# Relays.net
KiCad netlist of a schematic drawn in Altium Designer
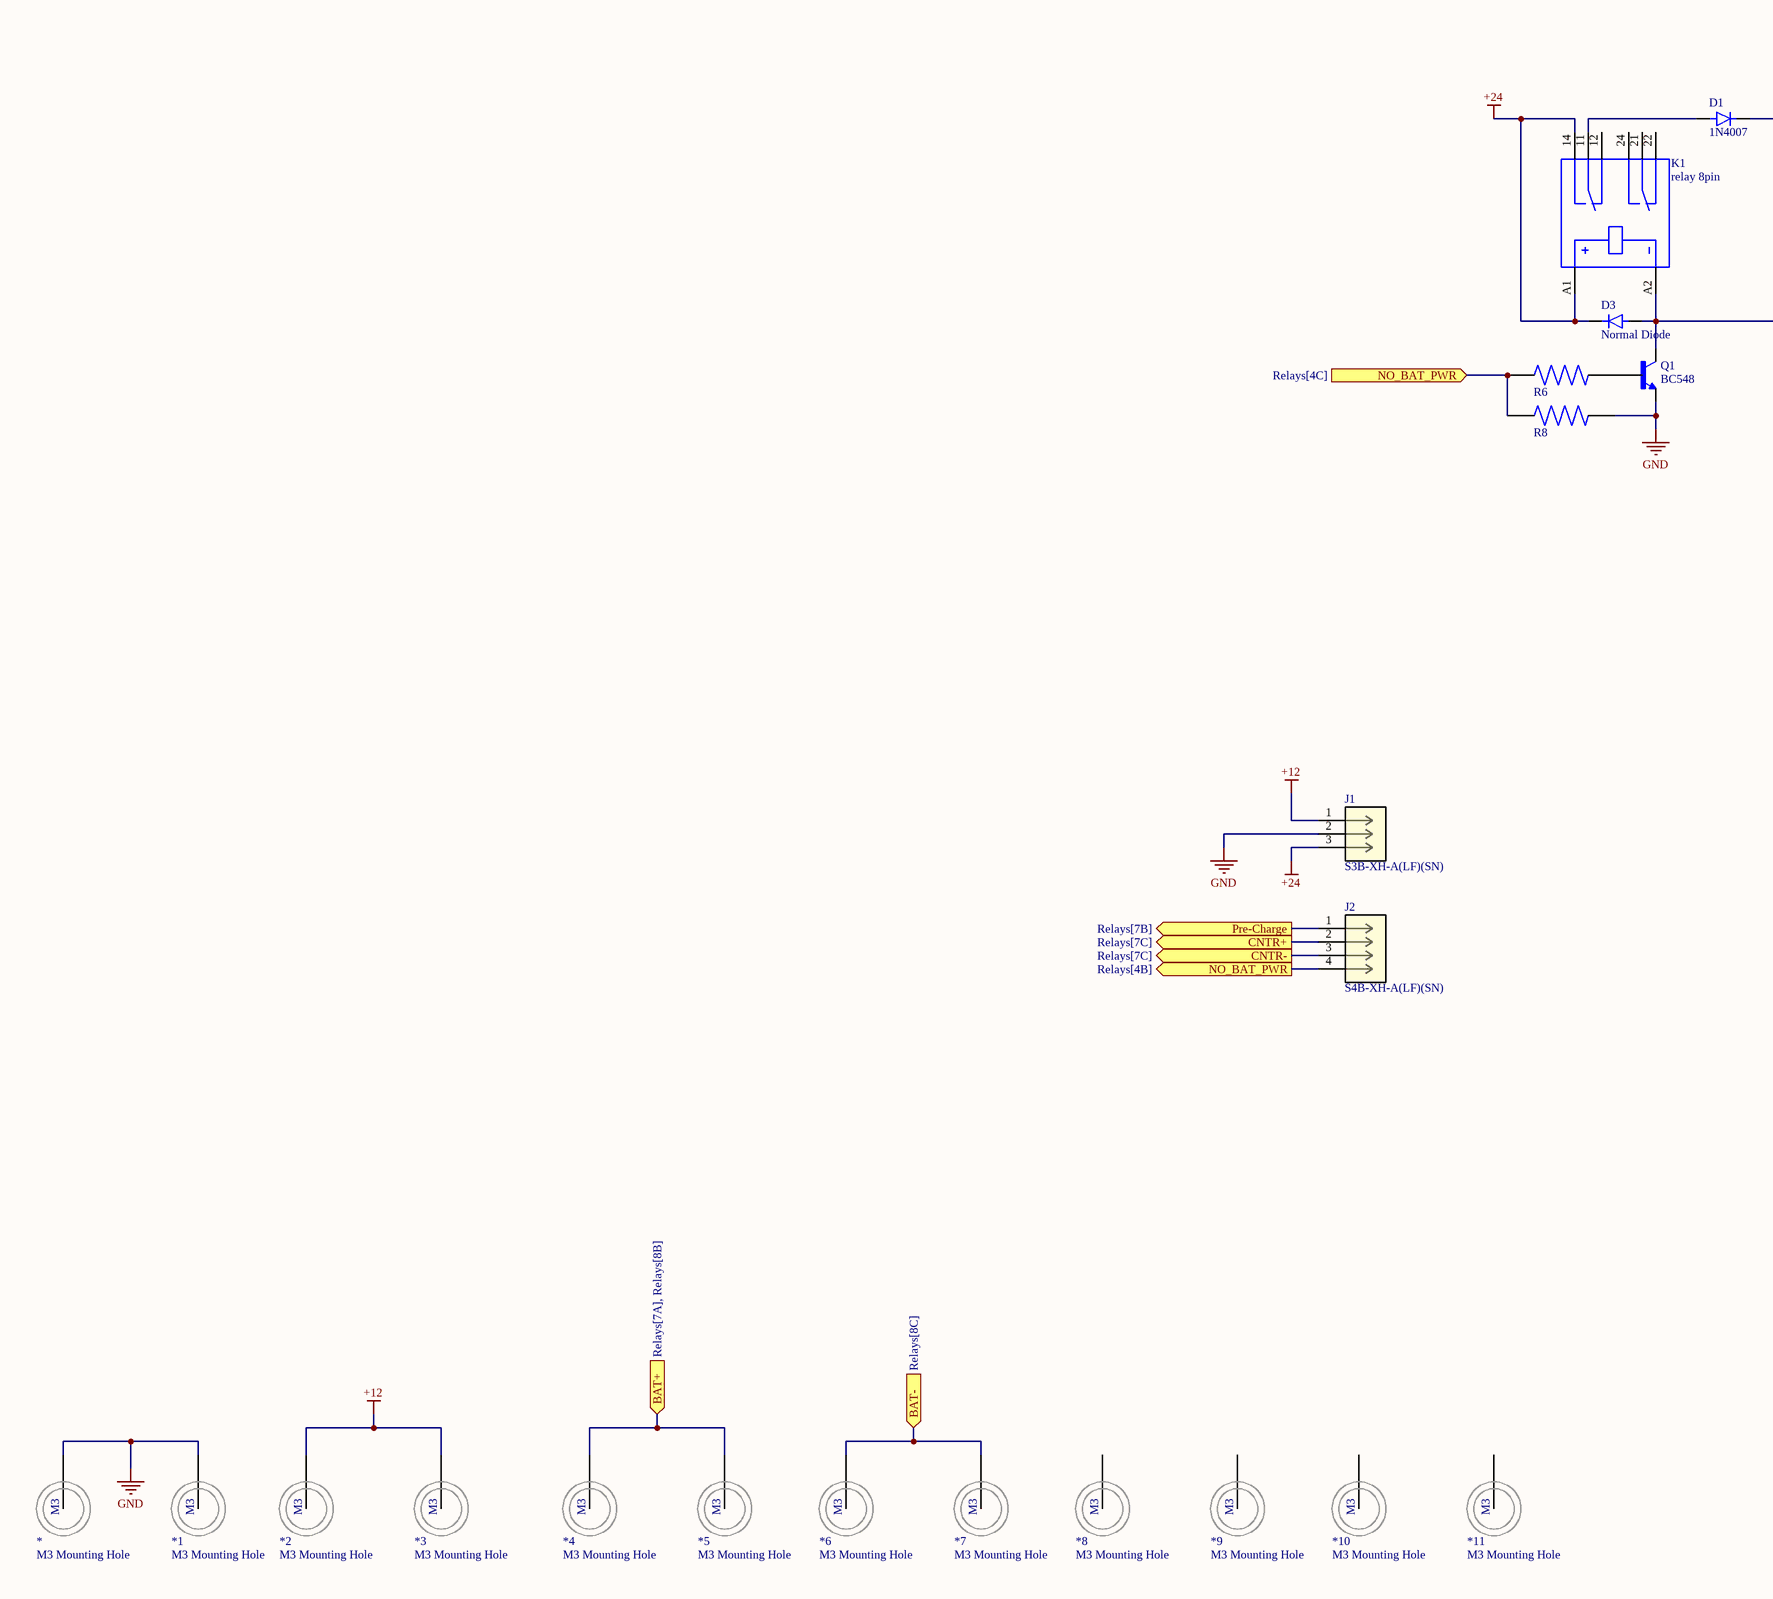
[diagram p0: Relays.SchDoc, left]
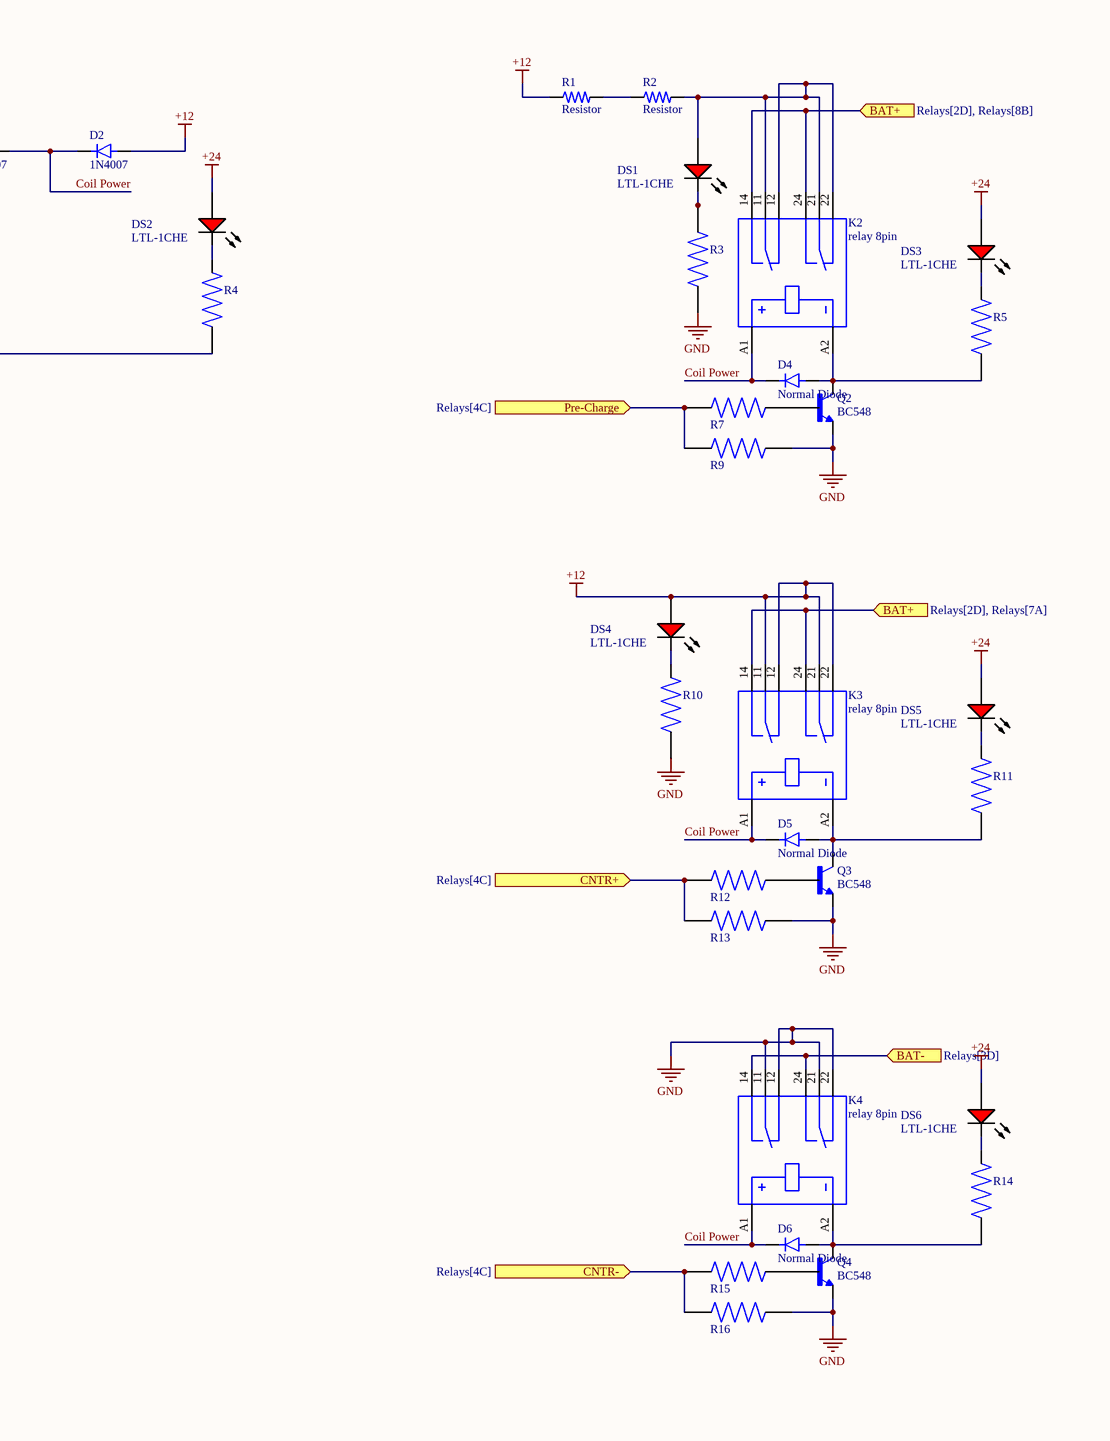
[diagram p1: Relays.SchDoc, right]

(export (version "E")
  (design (tool "Eeschema 10.0.6"))
  (components
    (comp (ref "*")
      (value "M3 Mounting Hole")
      (footprint "M3 - Mounting Hole")
      (libsource (lib "Connectors Through Hole") (part "M3 Mounting Hole"))
    )
    (comp (ref "*1")
      (value "M3 Mounting Hole")
      (footprint "M3 - Mounting Hole")
      (libsource (lib "Connectors Through Hole") (part "M3 Mounting Hole"))
    )
    (comp (ref "*2")
      (value "M3 Mounting Hole")
      (footprint "M3 - Mounting Hole")
      (libsource (lib "Connectors Through Hole") (part "M3 Mounting Hole"))
    )
    (comp (ref "*3")
      (value "M3 Mounting Hole")
      (footprint "M3 - Mounting Hole")
      (libsource (lib "Connectors Through Hole") (part "M3 Mounting Hole"))
    )
    (comp (ref "*4")
      (value "M3 Mounting Hole")
      (footprint "M3 - Mounting Hole")
      (libsource (lib "Connectors Through Hole") (part "M3 Mounting Hole"))
    )
    (comp (ref "*5")
      (value "M3 Mounting Hole")
      (footprint "M3 - Mounting Hole")
      (libsource (lib "Connectors Through Hole") (part "M3 Mounting Hole"))
    )
    (comp (ref "*6")
      (value "M3 Mounting Hole")
      (footprint "M3 - Mounting Hole")
      (libsource (lib "Connectors Through Hole") (part "M3 Mounting Hole"))
    )
    (comp (ref "*7")
      (value "M3 Mounting Hole")
      (footprint "M3 - Mounting Hole")
      (libsource (lib "Connectors Through Hole") (part "M3 Mounting Hole"))
    )
    (comp (ref "*8")
      (value "M3 Mounting Hole")
      (footprint "M3 - Mounting Hole")
      (libsource (lib "Connectors Through Hole") (part "M3 Mounting Hole"))
    )
    (comp (ref "*9")
      (value "M3 Mounting Hole")
      (footprint "M3 - Mounting Hole")
      (libsource (lib "Connectors Through Hole") (part "M3 Mounting Hole"))
    )
    (comp (ref "*10")
      (value "M3 Mounting Hole")
      (footprint "M3 - Mounting Hole")
      (libsource (lib "Connectors Through Hole") (part "M3 Mounting Hole"))
    )
    (comp (ref "*11")
      (value "M3 Mounting Hole")
      (footprint "M3 - Mounting Hole")
      (libsource (lib "Connectors Through Hole") (part "M3 Mounting Hole"))
    )
    (comp (ref "D1")
      (value "1N4007")
      (footprint "Common Trhough Hole")
      (fields (field (name "MF") "NTE Electronics, Inc."))
      (libsource (lib "Diodes Through Hole") (part "Normal Diode"))
    )
    (comp (ref "D2")
      (value "1N4007")
      (footprint "Common Trhough Hole")
      (fields (field (name "MF") "NTE Electronics, Inc."))
      (libsource (lib "Diodes Through Hole") (part "Normal Diode"))
    )
    (comp (ref "D3")
      (value "Normal Diode")
      (footprint "Common Trhough Hole")
      (fields (field (name "MF") "NTE Electronics, Inc.") (field (name "MP") "1N4007"))
      (libsource (lib "Diodes Through Hole") (part "Normal Diode"))
    )
    (comp (ref "D4")
      (value "Normal Diode")
      (footprint "Common Trhough Hole")
      (fields (field (name "MF") "NTE Electronics, Inc.") (field (name "MP") "1N4007"))
      (libsource (lib "Diodes Through Hole") (part "Normal Diode"))
    )
    (comp (ref "D5")
      (value "Normal Diode")
      (footprint "Common Trhough Hole")
      (fields (field (name "MF") "NTE Electronics, Inc.") (field (name "MP") "1N4007"))
      (libsource (lib "Diodes Through Hole") (part "Normal Diode"))
    )
    (comp (ref "D6")
      (value "Normal Diode")
      (footprint "Common Trhough Hole")
      (fields (field (name "MF") "NTE Electronics, Inc.") (field (name "MP") "1N4007"))
      (libsource (lib "Diodes Through Hole") (part "Normal Diode"))
    )
    (comp (ref "DS1")
      (value "LTL-1CHE")
      (footprint "LED_3mm")
      (description "Radial LED, 12.6 mcd, 20 mA, 2 V, -55 to 100 degC, 2-Pin THD, RoHS, Bulk")
      (fields (field (name "TOLERANCE") "20%"))
      (libsource (lib "MySCH_Library") (part "RED_LED 3mm"))
    )
    (comp (ref "DS2")
      (value "LTL-1CHE")
      (footprint "LED_3mm")
      (description "Radial LED, 12.6 mcd, 20 mA, 2 V, -55 to 100 degC, 2-Pin THD, RoHS, Bulk")
      (fields (field (name "TOLERANCE") "20%"))
      (libsource (lib "MySCH_Library") (part "RED_LED 3mm"))
    )
    (comp (ref "DS3")
      (value "LTL-1CHE")
      (footprint "LED_3mm")
      (description "Radial LED, 12.6 mcd, 20 mA, 2 V, -55 to 100 degC, 2-Pin THD, RoHS, Bulk")
      (fields (field (name "TOLERANCE") "20%"))
      (libsource (lib "MySCH_Library") (part "RED_LED 3mm"))
    )
    (comp (ref "DS4")
      (value "LTL-1CHE")
      (footprint "LED_3mm")
      (description "Radial LED, 12.6 mcd, 20 mA, 2 V, -55 to 100 degC, 2-Pin THD, RoHS, Bulk")
      (fields (field (name "TOLERANCE") "20%"))
      (libsource (lib "MySCH_Library") (part "RED_LED 3mm"))
    )
    (comp (ref "DS5")
      (value "LTL-1CHE")
      (footprint "LED_3mm")
      (description "Radial LED, 12.6 mcd, 20 mA, 2 V, -55 to 100 degC, 2-Pin THD, RoHS, Bulk")
      (fields (field (name "TOLERANCE") "20%"))
      (libsource (lib "MySCH_Library") (part "RED_LED 3mm"))
    )
    (comp (ref "DS6")
      (value "LTL-1CHE")
      (footprint "LED_3mm")
      (description "Radial LED, 12.6 mcd, 20 mA, 2 V, -55 to 100 degC, 2-Pin THD, RoHS, Bulk")
      (fields (field (name "TOLERANCE") "20%"))
      (libsource (lib "MySCH_Library") (part "RED_LED 3mm"))
    )
    (comp (ref "J1")
      (value "S3B-XH-A(LF)(SN)")
      (footprint "3P JST XH2.54mm 90º")
      (description "No Description Available")
      (fields (field (name "COPYRIGHT") "Copyright (C) 2024 Ultra Librarian. All rights reserved."))
      (libsource (lib "Connectors Through Hole") (part "3P JST XH2.54mm 90º"))
    )
    (comp (ref "J2")
      (value "S4B-XH-A(LF)(SN)")
      (footprint "4P JST XH2.54mm 90º")
      (description "No Description Available")
      (fields (field (name "COPYRIGHT") "Copyright (C) 2024 Ultra Librarian. All rights reserved."))
      (libsource (lib "Connectors Through Hole") (part "4P JST XH2.54mm 90º"))
    )
    (comp (ref "K1")
      (value "relay 8pin")
      (footprint "Relay socket 8pin")
      (description "General Purpose Relay DPDT _2 Form C_ 24VDC Coil Through Hole")
      (fields (field (name "MF") "TE Connectivity") (field (name "MP") "1-1393243-0"))
      (libsource (lib "MySCH_Library") (part "relay 8pin"))
    )
    (comp (ref "K2")
      (value "relay 8pin")
      (footprint "Relay socket 8pin")
      (description "General Purpose Relay DPDT _2 Form C_ 24VDC Coil Through Hole")
      (fields (field (name "MF") "TE Connectivity") (field (name "MP") "1-1393243-0"))
      (libsource (lib "MySCH_Library") (part "relay 8pin"))
    )
    (comp (ref "K3")
      (value "relay 8pin")
      (footprint "Relay socket 8pin")
      (description "General Purpose Relay DPDT _2 Form C_ 24VDC Coil Through Hole")
      (fields (field (name "MF") "TE Connectivity") (field (name "MP") "1-1393243-0"))
      (libsource (lib "MySCH_Library") (part "relay 8pin"))
    )
    (comp (ref "K4")
      (value "relay 8pin")
      (footprint "Relay socket 8pin")
      (description "General Purpose Relay DPDT _2 Form C_ 24VDC Coil Through Hole")
      (fields (field (name "MF") "TE Connectivity") (field (name "MP") "1-1393243-0"))
      (libsource (lib "MySCH_Library") (part "relay 8pin"))
    )
    (comp (ref "Q1")
      (value "BC548")
      (footprint "bc548")
      (description "Bipolar (BJT) Transistor NPN 30V 100mA 300MHz 500mW Through Hole TO-92-3")
      (fields (field (name "MF") "ON Semiconductor"))
      (libsource (lib "MySCH_Library") (part "BC548"))
    )
    (comp (ref "Q2")
      (value "BC548")
      (footprint "bc548")
      (description "Bipolar (BJT) Transistor NPN 30V 100mA 300MHz 500mW Through Hole TO-92-3")
      (fields (field (name "MF") "ON Semiconductor"))
      (libsource (lib "MySCH_Library") (part "BC548"))
    )
    (comp (ref "Q3")
      (value "BC548")
      (footprint "bc548")
      (description "Bipolar (BJT) Transistor NPN 30V 100mA 300MHz 500mW Through Hole TO-92-3")
      (fields (field (name "MF") "ON Semiconductor"))
      (libsource (lib "MySCH_Library") (part "BC548"))
    )
    (comp (ref "Q4")
      (value "BC548")
      (footprint "bc548")
      (description "Bipolar (BJT) Transistor NPN 30V 100mA 300MHz 500mW Through Hole TO-92-3")
      (fields (field (name "MF") "ON Semiconductor"))
      (libsource (lib "MySCH_Library") (part "BC548"))
    )
    (comp (ref "R1")
      (value "Resistor")
      (footprint "Resistor_Through Hole")
      (fields
        (field (name "MP") "2-2176053-0")
        (field (name "TOLERANCE") "1%")
        (field (name "MF") "TE Connectivity")
      )
      (libsource (lib "Resistors Through Hole") (part "Resistor"))
    )
    (comp (ref "R2")
      (value "Resistor")
      (footprint "Resistor_Through Hole")
      (fields
        (field (name "MP") "2-2176053-0")
        (field (name "TOLERANCE") "1%")
        (field (name "MF") "TE Connectivity")
      )
      (libsource (lib "Resistors Through Hole") (part "Resistor"))
    )
    (comp (ref "R3")
      (value "Resistor_Through Hole")
      (footprint "Resistor_Through Hole")
      (description "1.02 Ohms Â±1% 0.25W, 1/4W Through Hole Resistor Axial Metal Film")
      (fields (field (name "MP") "MFR-25FTE52-1R") (field (name "MF") "Yageo"))
      (libsource (lib "MySCH_Library") (part "Resistor_Through Hole"))
    )
    (comp (ref "R4")
      (value "Resistor_Through Hole")
      (footprint "Resistor_Through Hole")
      (description "1.02 Ohms Â±1% 0.25W, 1/4W Through Hole Resistor Axial Metal Film")
      (fields (field (name "MP") "MFR-25FTE52-1R") (field (name "MF") "Yageo"))
      (libsource (lib "MySCH_Library") (part "Resistor_Through Hole"))
    )
    (comp (ref "R5")
      (value "Resistor_Through Hole")
      (footprint "Resistor_Through Hole")
      (description "1.02 Ohms Â±1% 0.25W, 1/4W Through Hole Resistor Axial Metal Film")
      (fields (field (name "MP") "MFR-25FTE52-1R") (field (name "MF") "Yageo"))
      (libsource (lib "MySCH_Library") (part "Resistor_Through Hole"))
    )
    (comp (ref "R6")
      (value "Resistor_Through Hole")
      (footprint "Resistor_Through Hole")
      (description "1.02 Ohms Â±1% 0.25W, 1/4W Through Hole Resistor Axial Metal Film")
      (fields (field (name "MP") "MFR-25FTE52-1R") (field (name "MF") "Yageo"))
      (libsource (lib "MySCH_Library") (part "Resistor_Through Hole"))
    )
    (comp (ref "R7")
      (value "Resistor_Through Hole")
      (footprint "Resistor_Through Hole")
      (description "1.02 Ohms Â±1% 0.25W, 1/4W Through Hole Resistor Axial Metal Film")
      (fields (field (name "MP") "MFR-25FTE52-1R") (field (name "MF") "Yageo"))
      (libsource (lib "MySCH_Library") (part "Resistor_Through Hole"))
    )
    (comp (ref "R8")
      (value "Resistor_Through Hole")
      (footprint "Resistor_Through Hole")
      (description "1.02 Ohms Â±1% 0.25W, 1/4W Through Hole Resistor Axial Metal Film")
      (fields (field (name "MP") "MFR-25FTE52-1R") (field (name "MF") "Yageo"))
      (libsource (lib "MySCH_Library") (part "Resistor_Through Hole"))
    )
    (comp (ref "R9")
      (value "Resistor_Through Hole")
      (footprint "Resistor_Through Hole")
      (description "1.02 Ohms Â±1% 0.25W, 1/4W Through Hole Resistor Axial Metal Film")
      (fields (field (name "MP") "MFR-25FTE52-1R") (field (name "MF") "Yageo"))
      (libsource (lib "MySCH_Library") (part "Resistor_Through Hole"))
    )
    (comp (ref "R10")
      (value "Resistor_Through Hole")
      (footprint "Resistor_Through Hole")
      (description "1.02 Ohms Â±1% 0.25W, 1/4W Through Hole Resistor Axial Metal Film")
      (fields (field (name "MP") "MFR-25FTE52-1R") (field (name "MF") "Yageo"))
      (libsource (lib "MySCH_Library") (part "Resistor_Through Hole"))
    )
    (comp (ref "R11")
      (value "Resistor_Through Hole")
      (footprint "Resistor_Through Hole")
      (description "1.02 Ohms Â±1% 0.25W, 1/4W Through Hole Resistor Axial Metal Film")
      (fields (field (name "MP") "MFR-25FTE52-1R") (field (name "MF") "Yageo"))
      (libsource (lib "MySCH_Library") (part "Resistor_Through Hole"))
    )
    (comp (ref "R12")
      (value "Resistor_Through Hole")
      (footprint "Resistor_Through Hole")
      (description "1.02 Ohms Â±1% 0.25W, 1/4W Through Hole Resistor Axial Metal Film")
      (fields (field (name "MP") "MFR-25FTE52-1R") (field (name "MF") "Yageo"))
      (libsource (lib "MySCH_Library") (part "Resistor_Through Hole"))
    )
    (comp (ref "R13")
      (value "Resistor_Through Hole")
      (footprint "Resistor_Through Hole")
      (description "1.02 Ohms Â±1% 0.25W, 1/4W Through Hole Resistor Axial Metal Film")
      (fields (field (name "MP") "MFR-25FTE52-1R") (field (name "MF") "Yageo"))
      (libsource (lib "MySCH_Library") (part "Resistor_Through Hole"))
    )
    (comp (ref "R14")
      (value "Resistor_Through Hole")
      (footprint "Resistor_Through Hole")
      (description "1.02 Ohms Â±1% 0.25W, 1/4W Through Hole Resistor Axial Metal Film")
      (fields (field (name "MP") "MFR-25FTE52-1R") (field (name "MF") "Yageo"))
      (libsource (lib "MySCH_Library") (part "Resistor_Through Hole"))
    )
    (comp (ref "R15")
      (value "Resistor_Through Hole")
      (footprint "Resistor_Through Hole")
      (description "1.02 Ohms Â±1% 0.25W, 1/4W Through Hole Resistor Axial Metal Film")
      (fields (field (name "MP") "MFR-25FTE52-1R") (field (name "MF") "Yageo"))
      (libsource (lib "MySCH_Library") (part "Resistor_Through Hole"))
    )
    (comp (ref "R16")
      (value "Resistor_Through Hole")
      (footprint "Resistor_Through Hole")
      (description "1.02 Ohms Â±1% 0.25W, 1/4W Through Hole Resistor Axial Metal Film")
      (fields (field (name "MP") "MFR-25FTE52-1R") (field (name "MF") "Yageo"))
      (libsource (lib "MySCH_Library") (part "Resistor_Through Hole"))
    )
  )
  (nets
    (net (code "1") (name "+12") (class "Default")
      (node (ref "*2") (pin "1") (pinfunction "M3_1") (pintype "passive"))
      (node (ref "*3") (pin "1") (pinfunction "M3_1") (pintype "passive"))
      (node (ref "D2") (pin "2") (pinfunction "A_2") (pintype "passive"))
      (node (ref "DS4") (pin "1") (pinfunction "A_1") (pintype "passive"))
      (node (ref "J1") (pin "1") (pinfunction "1_1") (pintype "passive"))
      (node (ref "K3") (pin "11") (pinfunction "6_11") (pintype "passive"))
      (node (ref "K3") (pin "12") (pinfunction "7_12") (pintype "passive"))
      (node (ref "K3") (pin "21") (pinfunction "3_21") (pintype "passive"))
      (node (ref "K3") (pin "22") (pinfunction "2_22") (pintype "passive"))
      (node (ref "R1") (pin "1") (pinfunction "1_1") (pintype "passive"))
    )
    (net (code "2") (name "+24") (class "Default")
      (node (ref "D3") (pin "1") (pinfunction "K_1") (pintype "passive"))
      (node (ref "DS2") (pin "1") (pinfunction "A_1") (pintype "passive"))
      (node (ref "DS3") (pin "1") (pinfunction "A_1") (pintype "passive"))
      (node (ref "DS5") (pin "1") (pinfunction "A_1") (pintype "passive"))
      (node (ref "DS6") (pin "1") (pinfunction "A_1") (pintype "passive"))
      (node (ref "J1") (pin "3") (pinfunction "3_3") (pintype "passive"))
      (node (ref "K1") (pin "14") (pinfunction "5_14") (pintype "passive"))
      (node (ref "K1") (pin "A1") (pinfunction "1_A1") (pintype "passive"))
    )
    (net (code "3") (name "/BAT+") (class "Default")
      (node (ref "*4") (pin "1") (pinfunction "M3_1") (pintype "passive"))
      (node (ref "*5") (pin "1") (pinfunction "M3_1") (pintype "passive"))
      (node (ref "K2") (pin "14") (pinfunction "5_14") (pintype "passive"))
      (node (ref "K2") (pin "24") (pinfunction "4_24") (pintype "passive"))
      (node (ref "K3") (pin "14") (pinfunction "5_14") (pintype "passive"))
      (node (ref "K3") (pin "24") (pinfunction "4_24") (pintype "passive"))
    )
    (net (code "4") (name "/BAT-") (class "Default")
      (node (ref "*6") (pin "1") (pinfunction "M3_1") (pintype "passive"))
      (node (ref "*7") (pin "1") (pinfunction "M3_1") (pintype "passive"))
      (node (ref "K4") (pin "14") (pinfunction "5_14") (pintype "passive"))
      (node (ref "K4") (pin "24") (pinfunction "4_24") (pintype "passive"))
    )
    (net (code "5") (name "/CNTR+") (class "Default")
      (node (ref "J2") (pin "2") (pinfunction "2_2") (pintype "passive"))
      (node (ref "R12") (pin "2") (pinfunction "2_2") (pintype "passive"))
      (node (ref "R13") (pin "2") (pinfunction "2_2") (pintype "passive"))
    )
    (net (code "6") (name "/CNTR-") (class "Default")
      (node (ref "J2") (pin "3") (pinfunction "3_3") (pintype "passive"))
      (node (ref "R15") (pin "2") (pinfunction "2_2") (pintype "passive"))
      (node (ref "R16") (pin "2") (pinfunction "2_2") (pintype "passive"))
    )
    (net (code "7") (name "/Coil Power") (class "Default")
      (node (ref "D1") (pin "1") (pinfunction "K_1") (pintype "passive"))
      (node (ref "D2") (pin "1") (pinfunction "K_1") (pintype "passive"))
      (node (ref "D4") (pin "1") (pinfunction "K_1") (pintype "passive"))
      (node (ref "D5") (pin "1") (pinfunction "K_1") (pintype "passive"))
      (node (ref "D6") (pin "1") (pinfunction "K_1") (pintype "passive"))
      (node (ref "K2") (pin "A1") (pinfunction "1_A1") (pintype "passive"))
      (node (ref "K3") (pin "A1") (pinfunction "1_A1") (pintype "passive"))
      (node (ref "K4") (pin "A1") (pinfunction "1_A1") (pintype "passive"))
    )
    (net (code "8") (name "/NO_BAT_PWR") (class "Default")
      (node (ref "J2") (pin "4") (pinfunction "4_4") (pintype "passive"))
      (node (ref "R6") (pin "2") (pinfunction "2_2") (pintype "passive"))
      (node (ref "R8") (pin "2") (pinfunction "2_2") (pintype "passive"))
    )
    (net (code "9") (name "/Pre-Charge") (class "Default")
      (node (ref "J2") (pin "1") (pinfunction "1_1") (pintype "passive"))
      (node (ref "R7") (pin "2") (pinfunction "2_2") (pintype "passive"))
      (node (ref "R9") (pin "2") (pinfunction "2_2") (pintype "passive"))
    )
    (net (code "10") (name "GND") (class "Default")
      (node (ref "*") (pin "1") (pinfunction "M3_1") (pintype "passive"))
      (node (ref "*1") (pin "1") (pinfunction "M3_1") (pintype "passive"))
      (node (ref "J1") (pin "2") (pinfunction "2_2") (pintype "passive"))
      (node (ref "K4") (pin "11") (pinfunction "6_11") (pintype "passive"))
      (node (ref "K4") (pin "12") (pinfunction "7_12") (pintype "passive"))
      (node (ref "K4") (pin "21") (pinfunction "3_21") (pintype "passive"))
      (node (ref "K4") (pin "22") (pinfunction "2_22") (pintype "passive"))
      (node (ref "Q1") (pin "3") (pinfunction "E_3") (pintype "passive"))
      (node (ref "Q2") (pin "3") (pinfunction "E_3") (pintype "passive"))
      (node (ref "Q3") (pin "3") (pinfunction "E_3") (pintype "passive"))
      (node (ref "Q4") (pin "3") (pinfunction "E_3") (pintype "passive"))
      (node (ref "R10") (pin "2") (pinfunction "2_2") (pintype "passive"))
      (node (ref "R13") (pin "1") (pinfunction "1_1") (pintype "passive"))
      (node (ref "R16") (pin "1") (pinfunction "1_1") (pintype "passive"))
      (node (ref "R3") (pin "2") (pinfunction "2_2") (pintype "passive"))
      (node (ref "R8") (pin "1") (pinfunction "1_1") (pintype "passive"))
      (node (ref "R9") (pin "1") (pinfunction "1_1") (pintype "passive"))
    )
    (net (code "11") (name "Net-(D1-A)") (class "Default")
      (node (ref "D1") (pin "2") (pinfunction "A_2") (pintype "passive"))
      (node (ref "K1") (pin "11") (pinfunction "6_11") (pintype "passive"))
    )
    (net (code "12") (name "Net-(D3-A)") (class "Default")
      (node (ref "D3") (pin "2") (pinfunction "A_2") (pintype "passive"))
      (node (ref "K1") (pin "A2") (pinfunction "8_A2") (pintype "passive"))
      (node (ref "Q1") (pin "1") (pinfunction "C_1") (pintype "passive"))
      (node (ref "R4") (pin "2") (pinfunction "2_2") (pintype "passive"))
    )
    (net (code "13") (name "Net-(D4-A)") (class "Default")
      (node (ref "D4") (pin "2") (pinfunction "A_2") (pintype "passive"))
      (node (ref "K2") (pin "A2") (pinfunction "8_A2") (pintype "passive"))
      (node (ref "Q2") (pin "1") (pinfunction "C_1") (pintype "passive"))
      (node (ref "R5") (pin "2") (pinfunction "2_2") (pintype "passive"))
    )
    (net (code "14") (name "Net-(D5-A)") (class "Default")
      (node (ref "D5") (pin "2") (pinfunction "A_2") (pintype "passive"))
      (node (ref "K3") (pin "A2") (pinfunction "8_A2") (pintype "passive"))
      (node (ref "Q3") (pin "1") (pinfunction "C_1") (pintype "passive"))
      (node (ref "R11") (pin "2") (pinfunction "2_2") (pintype "passive"))
    )
    (net (code "15") (name "Net-(D6-A)") (class "Default")
      (node (ref "D6") (pin "2") (pinfunction "A_2") (pintype "passive"))
      (node (ref "K4") (pin "A2") (pinfunction "8_A2") (pintype "passive"))
      (node (ref "Q4") (pin "1") (pinfunction "C_1") (pintype "passive"))
      (node (ref "R14") (pin "2") (pinfunction "2_2") (pintype "passive"))
    )
    (net (code "16") (name "Net-(DS1-A)") (class "Default")
      (node (ref "DS1") (pin "1") (pinfunction "A_1") (pintype "passive"))
      (node (ref "K2") (pin "11") (pinfunction "6_11") (pintype "passive"))
      (node (ref "K2") (pin "12") (pinfunction "7_12") (pintype "passive"))
      (node (ref "K2") (pin "21") (pinfunction "3_21") (pintype "passive"))
      (node (ref "K2") (pin "22") (pinfunction "2_22") (pintype "passive"))
      (node (ref "R2") (pin "2") (pinfunction "2_2") (pintype "passive"))
    )
    (net (code "17") (name "Net-(DS1-K)") (class "Default")
      (node (ref "DS1") (pin "2") (pinfunction "K_2") (pintype "passive"))
      (node (ref "R3") (pin "1") (pinfunction "1_1") (pintype "passive"))
    )
    (net (code "18") (name "Net-(DS2-K)") (class "Default")
      (node (ref "DS2") (pin "2") (pinfunction "K_2") (pintype "passive"))
      (node (ref "R4") (pin "1") (pinfunction "1_1") (pintype "passive"))
    )
    (net (code "19") (name "Net-(DS3-K)") (class "Default")
      (node (ref "DS3") (pin "2") (pinfunction "K_2") (pintype "passive"))
      (node (ref "R5") (pin "1") (pinfunction "1_1") (pintype "passive"))
    )
    (net (code "20") (name "Net-(DS4-K)") (class "Default")
      (node (ref "DS4") (pin "2") (pinfunction "K_2") (pintype "passive"))
      (node (ref "R10") (pin "1") (pinfunction "1_1") (pintype "passive"))
    )
    (net (code "21") (name "Net-(DS5-K)") (class "Default")
      (node (ref "DS5") (pin "2") (pinfunction "K_2") (pintype "passive"))
      (node (ref "R11") (pin "1") (pinfunction "1_1") (pintype "passive"))
    )
    (net (code "22") (name "Net-(DS6-K)") (class "Default")
      (node (ref "DS6") (pin "2") (pinfunction "K_2") (pintype "passive"))
      (node (ref "R14") (pin "1") (pinfunction "1_1") (pintype "passive"))
    )
    (net (code "23") (name "Net-(Q1-B)") (class "Default")
      (node (ref "Q1") (pin "2") (pinfunction "B_2") (pintype "passive"))
      (node (ref "R6") (pin "1") (pinfunction "1_1") (pintype "passive"))
    )
    (net (code "24") (name "Net-(Q2-B)") (class "Default")
      (node (ref "Q2") (pin "2") (pinfunction "B_2") (pintype "passive"))
      (node (ref "R7") (pin "1") (pinfunction "1_1") (pintype "passive"))
    )
    (net (code "25") (name "Net-(Q3-B)") (class "Default")
      (node (ref "Q3") (pin "2") (pinfunction "B_2") (pintype "passive"))
      (node (ref "R12") (pin "1") (pinfunction "1_1") (pintype "passive"))
    )
    (net (code "26") (name "Net-(Q4-B)") (class "Default")
      (node (ref "Q4") (pin "2") (pinfunction "B_2") (pintype "passive"))
      (node (ref "R15") (pin "1") (pinfunction "1_1") (pintype "passive"))
    )
    (net (code "27") (name "Net-(R1-Pad2)") (class "Default")
      (node (ref "R1") (pin "2") (pinfunction "2_2") (pintype "passive"))
      (node (ref "R2") (pin "1") (pinfunction "1_1") (pintype "passive"))
    )
    (net (code "28") (name "unconnected-(*8-M3-Pad1)") (class "Default")
      (node (ref "*8") (pin "1") (pinfunction "M3_1") (pintype "passive"))
    )
    (net (code "29") (name "unconnected-(*9-M3-Pad1)") (class "Default")
      (node (ref "*9") (pin "1") (pinfunction "M3_1") (pintype "passive"))
    )
    (net (code "30") (name "unconnected-(*10-M3-Pad1)") (class "Default")
      (node (ref "*10") (pin "1") (pinfunction "M3_1") (pintype "passive"))
    )
    (net (code "31") (name "unconnected-(*11-M3-Pad1)") (class "Default")
      (node (ref "*11") (pin "1") (pinfunction "M3_1") (pintype "passive"))
    )
    (net (code "32") (name "unconnected-(K1-2-Pad22)") (class "Default")
      (node (ref "K1") (pin "22") (pinfunction "2_22") (pintype "passive"))
    )
    (net (code "33") (name "unconnected-(K1-3-Pad21)") (class "Default")
      (node (ref "K1") (pin "21") (pinfunction "3_21") (pintype "passive"))
    )
    (net (code "34") (name "unconnected-(K1-4-Pad24)") (class "Default")
      (node (ref "K1") (pin "24") (pinfunction "4_24") (pintype "passive"))
    )
    (net (code "35") (name "unconnected-(K1-7-Pad12)") (class "Default")
      (node (ref "K1") (pin "12") (pinfunction "7_12") (pintype "passive"))
    )
  )
)
